# Motor.net
KiCad netlist of a schematic drawn in EAGLE
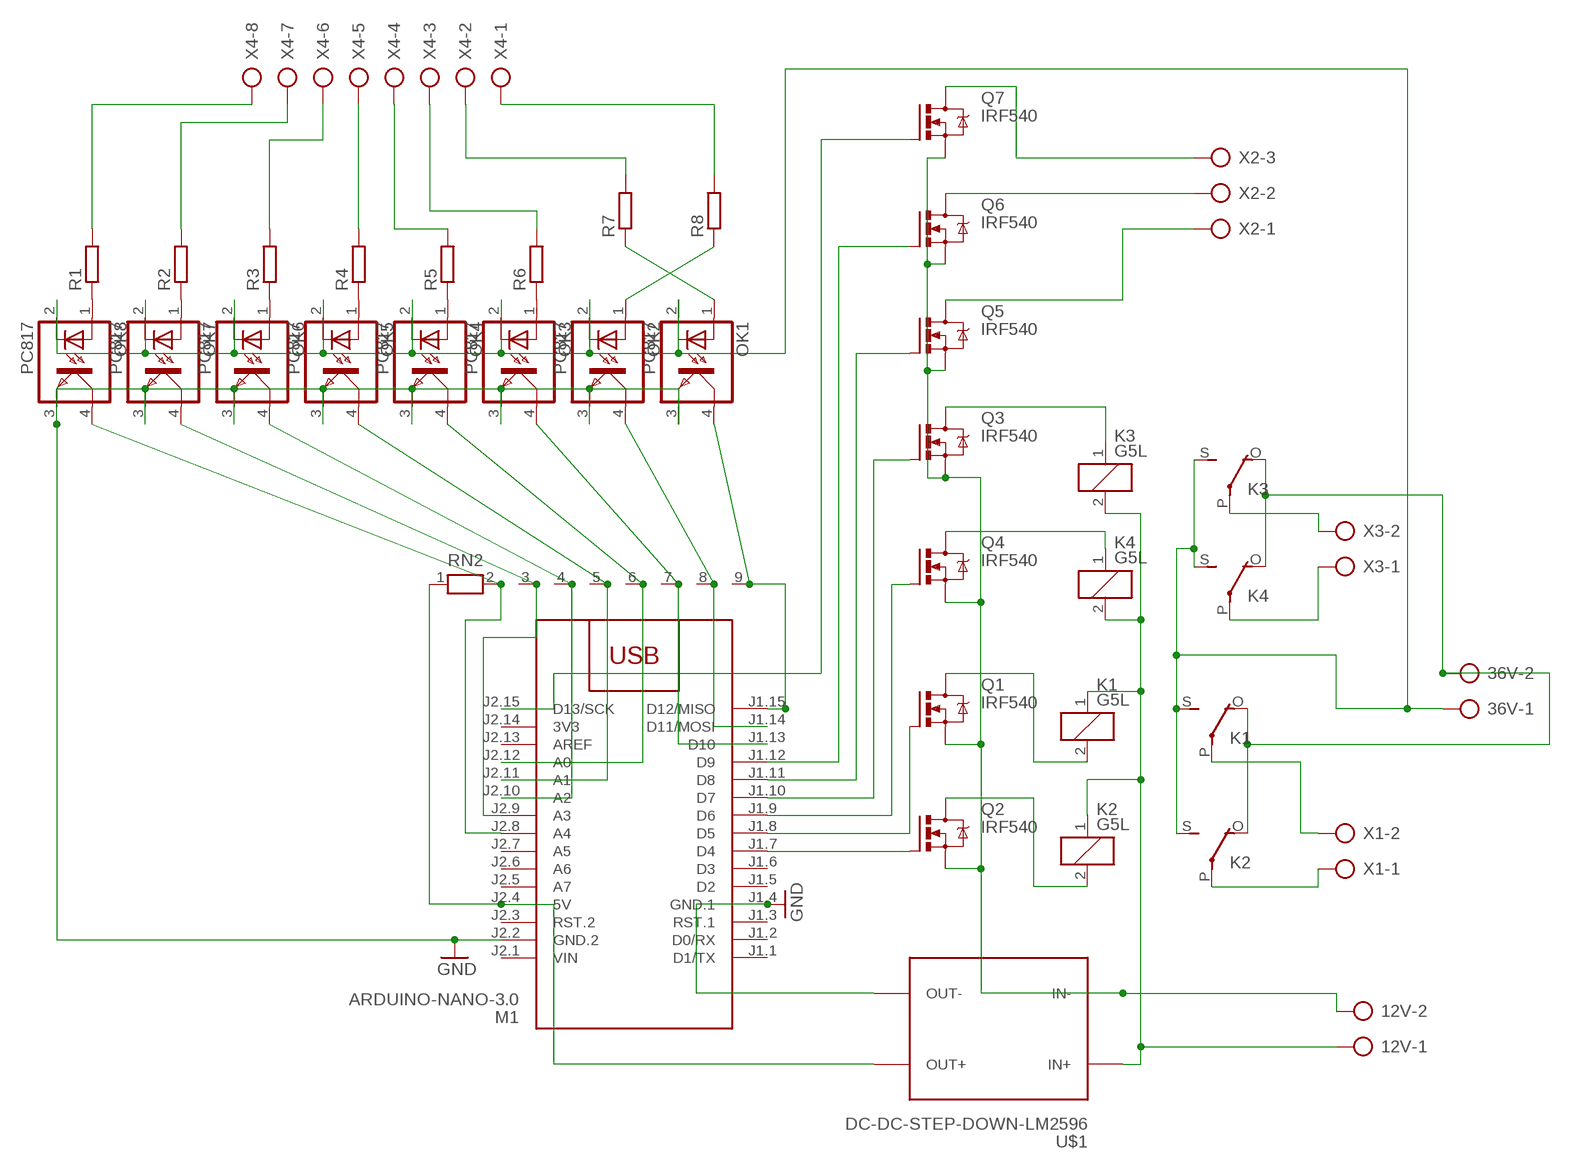
[diagram p0: schematic, sheet 1]

(export (version "E")
  (design (tool "Eeschema 10.0.6"))
  (components
    (comp (ref "12V")
      (value "AK300/2")
      (footprint "eagle-import:AK300_2")
      (libsource (lib "eagle-import") (part "AK300/2"))
    )
    (comp (ref "36V")
      (value "AK300/2")
      (footprint "eagle-import:AK300_2")
      (libsource (lib "eagle-import") (part "AK300/2"))
    )
    (comp (ref "K1")
      (value "G5L")
      (footprint "eagle-import:G5LE")
      (libsource (lib "eagle-import") (part "G5L"))
    )
    (comp (ref "K2")
      (value "G5L")
      (footprint "eagle-import:G5LE")
      (libsource (lib "eagle-import") (part "G5L"))
    )
    (comp (ref "K3")
      (value "G5L")
      (footprint "eagle-import:G5LE")
      (libsource (lib "eagle-import") (part "G5L"))
    )
    (comp (ref "K4")
      (value "G5L")
      (footprint "eagle-import:G5LE")
      (libsource (lib "eagle-import") (part "G5L"))
    )
    (comp (ref "M1")
      (value "ARDUINO-NANO-3.0")
      (footprint "eagle-import:ARDUINO-NANO-3.0")
      (libsource (lib "eagle-import") (part "ARDUINO-NANO-3.0"))
    )
    (comp (ref "OK1")
      (value "PC817")
      (footprint "eagle-import:DIL04")
      (fields (field (name "MPN") "PC817X4J000F"))
      (libsource (lib "eagle-import") (part "PC817"))
    )
    (comp (ref "OK2")
      (value "PC817")
      (footprint "eagle-import:DIL04")
      (fields (field (name "MPN") "PC817X4J000F"))
      (libsource (lib "eagle-import") (part "PC817"))
    )
    (comp (ref "OK3")
      (value "PC817")
      (footprint "eagle-import:DIL04")
      (fields (field (name "MPN") "PC817X4J000F"))
      (libsource (lib "eagle-import") (part "PC817"))
    )
    (comp (ref "OK4")
      (value "PC817")
      (footprint "eagle-import:DIL04")
      (fields (field (name "MPN") "PC817X4J000F"))
      (libsource (lib "eagle-import") (part "PC817"))
    )
    (comp (ref "OK5")
      (value "PC817")
      (footprint "eagle-import:DIL04")
      (fields (field (name "MPN") "PC817X4J000F"))
      (libsource (lib "eagle-import") (part "PC817"))
    )
    (comp (ref "OK6")
      (value "PC817")
      (footprint "eagle-import:DIL04")
      (fields (field (name "MPN") "PC817X4J000F"))
      (libsource (lib "eagle-import") (part "PC817"))
    )
    (comp (ref "OK7")
      (value "PC817")
      (footprint "eagle-import:DIL04")
      (fields (field (name "MPN") "PC817X4J000F"))
      (libsource (lib "eagle-import") (part "PC817"))
    )
    (comp (ref "OK8")
      (value "PC817")
      (footprint "eagle-import:DIL04")
      (fields (field (name "MPN") "PC817X4J000F"))
      (libsource (lib "eagle-import") (part "PC817"))
    )
    (comp (ref "Q1")
      (value "IRF540")
      (footprint "eagle-import:TO220BV")
      (libsource (lib "eagle-import") (part "IRF540"))
    )
    (comp (ref "Q2")
      (value "IRF540")
      (footprint "eagle-import:TO220BV")
      (libsource (lib "eagle-import") (part "IRF540"))
    )
    (comp (ref "Q3")
      (value "IRF540")
      (footprint "eagle-import:TO220BV")
      (libsource (lib "eagle-import") (part "IRF540"))
    )
    (comp (ref "Q4")
      (value "IRF540")
      (footprint "eagle-import:TO220BV")
      (libsource (lib "eagle-import") (part "IRF540"))
    )
    (comp (ref "Q5")
      (value "IRF540")
      (footprint "eagle-import:TO220BV")
      (libsource (lib "eagle-import") (part "IRF540"))
    )
    (comp (ref "Q6")
      (value "IRF540")
      (footprint "eagle-import:TO220BV")
      (libsource (lib "eagle-import") (part "IRF540"))
    )
    (comp (ref "Q7")
      (value "IRF540")
      (footprint "eagle-import:TO220BV")
      (libsource (lib "eagle-import") (part "IRF540"))
    )
    (comp (ref "R1")
      (value "R-EU_0204/7")
      (footprint "eagle-import:0204_7")
      (libsource (lib "eagle-import") (part "R-EU_0204/7"))
    )
    (comp (ref "R2")
      (value "R-EU_0204/7")
      (footprint "eagle-import:0204_7")
      (libsource (lib "eagle-import") (part "R-EU_0204/7"))
    )
    (comp (ref "R3")
      (value "R-EU_0204/7")
      (footprint "eagle-import:0204_7")
      (libsource (lib "eagle-import") (part "R-EU_0204/7"))
    )
    (comp (ref "R4")
      (value "R-EU_0204/7")
      (footprint "eagle-import:0204_7")
      (libsource (lib "eagle-import") (part "R-EU_0204/7"))
    )
    (comp (ref "R5")
      (value "R-EU_0204/7")
      (footprint "eagle-import:0204_7")
      (libsource (lib "eagle-import") (part "R-EU_0204/7"))
    )
    (comp (ref "R6")
      (value "R-EU_0204/7")
      (footprint "eagle-import:0204_7")
      (libsource (lib "eagle-import") (part "R-EU_0204/7"))
    )
    (comp (ref "R7")
      (value "R-EU_0204/7")
      (footprint "eagle-import:0204_7")
      (libsource (lib "eagle-import") (part "R-EU_0204/7"))
    )
    (comp (ref "R8")
      (value "R-EU_0204/7")
      (footprint "eagle-import:0204_7")
      (libsource (lib "eagle-import") (part "R-EU_0204/7"))
    )
    (comp (ref "RN2")
      (value "RN08")
      (footprint "eagle-import:RN-9")
      (libsource (lib "eagle-import") (part "RN08"))
    )
    (comp (ref "U$1")
      (value "DC-DC-STEP-DOWN-LM2596")
      (footprint "eagle-import:DC-DC-STEP-DOWN-LM2596")
      (libsource (lib "eagle-import") (part "DC-DC-STEP-DOWN-LM2596"))
    )
    (comp (ref "X1")
      (value "AK300/2")
      (footprint "eagle-import:AK300_2")
      (libsource (lib "eagle-import") (part "AK300/2"))
    )
    (comp (ref "X2")
      (value "AK300/3")
      (footprint "eagle-import:AK300_3")
      (libsource (lib "eagle-import") (part "AK300/3"))
    )
    (comp (ref "X3")
      (value "AK300/2")
      (footprint "eagle-import:AK300_2")
      (libsource (lib "eagle-import") (part "AK300/2"))
    )
    (comp (ref "X4")
      (value "AK300/8")
      (footprint "eagle-import:AK300_8")
      (libsource (lib "eagle-import") (part "AK300/8"))
    )
  )
  (nets
    (net (code "1") (name "/3V3") (class "Default")
      (node (ref "M1") (pin "J2.14") (pinfunction "3V3_J2.14") (pintype "power_in"))
    )
    (net (code "2") (name "/VIN") (class "Default")
      (node (ref "M1") (pin "J2.1") (pinfunction "VIN_J2.1") (pintype "power_in"))
    )
    (net (code "3") (name "GND") (class "Default")
      (node (ref "M1") (pin "J1.4") (pinfunction "GND.1_J1.4") (pintype "power_in"))
      (node (ref "M1") (pin "J2.2") (pinfunction "GND.2_J2.2") (pintype "power_in"))
      (node (ref "OK1") (pin "3") (pinfunction "EMIT_3") (pintype "passive"))
      (node (ref "OK2") (pin "3") (pinfunction "EMIT_3") (pintype "passive"))
      (node (ref "OK3") (pin "3") (pinfunction "EMIT_3") (pintype "passive"))
      (node (ref "OK4") (pin "3") (pinfunction "EMIT_3") (pintype "passive"))
      (node (ref "OK5") (pin "3") (pinfunction "EMIT_3") (pintype "passive"))
      (node (ref "OK6") (pin "3") (pinfunction "EMIT_3") (pintype "passive"))
      (node (ref "OK7") (pin "3") (pinfunction "EMIT_3") (pintype "passive"))
      (node (ref "OK8") (pin "3") (pinfunction "EMIT_3") (pintype "passive"))
      (node (ref "U$1") (pin "OUT-") (pinfunction "OUT-_OUT-") (pintype "bidirectional"))
    )
    (net (code "4") (name "Net-(12VA-KL)") (class "Default")
      (node (ref "12V") (pin "1") (pinfunction "KL_1") (pintype "passive"))
      (node (ref "K1") (pin "1") (pinfunction "1_1") (pintype "passive"))
      (node (ref "K2") (pin "1") (pinfunction "1_1") (pintype "passive"))
      (node (ref "K3") (pin "2") (pinfunction "2_2") (pintype "passive"))
      (node (ref "K4") (pin "2") (pinfunction "2_2") (pintype "passive"))
      (node (ref "U$1") (pin "IN+") (pinfunction "IN+_IN+") (pintype "bidirectional"))
    )
    (net (code "5") (name "Net-(12VB-KL)") (class "Default")
      (node (ref "12V") (pin "2") (pinfunction "KL_2") (pintype "passive"))
      (node (ref "Q1") (pin "S") (pinfunction "S_S") (pintype "passive"))
      (node (ref "Q2") (pin "S") (pinfunction "S_S") (pintype "passive"))
      (node (ref "Q3") (pin "S") (pinfunction "S_S") (pintype "passive"))
      (node (ref "Q4") (pin "S") (pinfunction "S_S") (pintype "passive"))
      (node (ref "Q5") (pin "S") (pinfunction "S_S") (pintype "passive"))
      (node (ref "Q6") (pin "S") (pinfunction "S_S") (pintype "passive"))
      (node (ref "Q7") (pin "S") (pinfunction "S_S") (pintype "passive"))
      (node (ref "U$1") (pin "IN-") (pinfunction "IN-_IN-") (pintype "bidirectional"))
    )
    (net (code "6") (name "Net-(36VA-KL)") (class "Default")
      (node (ref "36V") (pin "1") (pinfunction "KL_1") (pintype "passive"))
      (node (ref "K1") (pin "S") (pinfunction "S_S") (pintype "passive"))
      (node (ref "K2") (pin "S") (pinfunction "S_S") (pintype "passive"))
      (node (ref "K3") (pin "S") (pinfunction "S_S") (pintype "passive"))
      (node (ref "K4") (pin "S") (pinfunction "S_S") (pintype "passive"))
      (node (ref "OK1") (pin "2") (pinfunction "C_2") (pintype "passive"))
      (node (ref "OK2") (pin "2") (pinfunction "C_2") (pintype "passive"))
      (node (ref "OK3") (pin "2") (pinfunction "C_2") (pintype "passive"))
      (node (ref "OK4") (pin "2") (pinfunction "C_2") (pintype "passive"))
      (node (ref "OK5") (pin "2") (pinfunction "C_2") (pintype "passive"))
      (node (ref "OK6") (pin "2") (pinfunction "C_2") (pintype "passive"))
      (node (ref "OK7") (pin "2") (pinfunction "C_2") (pintype "passive"))
      (node (ref "OK8") (pin "2") (pinfunction "C_2") (pintype "passive"))
    )
    (net (code "7") (name "Net-(36VB-KL)") (class "Default")
      (node (ref "36V") (pin "2") (pinfunction "KL_2") (pintype "passive"))
      (node (ref "K1") (pin "O") (pinfunction "O_O") (pintype "passive"))
      (node (ref "K2") (pin "O") (pinfunction "O_O") (pintype "passive"))
      (node (ref "K3") (pin "O") (pinfunction "O_O") (pintype "passive"))
      (node (ref "K4") (pin "O") (pinfunction "O_O") (pintype "passive"))
    )
    (net (code "8") (name "Net-(K1-Pad2)") (class "Default")
      (node (ref "K1") (pin "2") (pinfunction "2_2") (pintype "passive"))
      (node (ref "Q1") (pin "D") (pinfunction "D_D") (pintype "passive"))
    )
    (net (code "9") (name "Net-(K2-Pad2)") (class "Default")
      (node (ref "K2") (pin "2") (pinfunction "2_2") (pintype "passive"))
      (node (ref "Q2") (pin "D") (pinfunction "D_D") (pintype "passive"))
    )
    (net (code "10") (name "Net-(K3-Pad1)") (class "Default")
      (node (ref "K3") (pin "1") (pinfunction "1_1") (pintype "passive"))
      (node (ref "Q3") (pin "D") (pinfunction "D_D") (pintype "passive"))
    )
    (net (code "11") (name "Net-(K4-Pad1)") (class "Default")
      (node (ref "K4") (pin "1") (pinfunction "1_1") (pintype "passive"))
      (node (ref "Q4") (pin "D") (pinfunction "D_D") (pintype "passive"))
    )
    (net (code "12") (name "Net-(M1-5V)") (class "Default")
      (node (ref "M1") (pin "J2.4") (pinfunction "5V_J2.4") (pintype "power_in"))
      (node (ref "RN2") (pin "1") (pinfunction "1_1") (pintype "passive"))
      (node (ref "U$1") (pin "OUT+") (pinfunction "OUT+_OUT+") (pintype "bidirectional"))
    )
    (net (code "13") (name "Net-(M1-A0)") (class "Default")
      (node (ref "M1") (pin "J2.12") (pinfunction "A0_J2.12") (pintype "bidirectional"))
      (node (ref "OK4") (pin "4") (pinfunction "COL_4") (pintype "passive"))
      (node (ref "RN2") (pin "6") (pinfunction "6_6") (pintype "passive"))
    )
    (net (code "14") (name "Net-(M1-A1)") (class "Default")
      (node (ref "M1") (pin "J2.11") (pinfunction "A1_J2.11") (pintype "bidirectional"))
      (node (ref "OK5") (pin "4") (pinfunction "COL_4") (pintype "passive"))
      (node (ref "RN2") (pin "5") (pinfunction "5_5") (pintype "passive"))
    )
    (net (code "15") (name "Net-(M1-A2)") (class "Default")
      (node (ref "M1") (pin "J2.10") (pinfunction "A2_J2.10") (pintype "bidirectional"))
      (node (ref "OK6") (pin "4") (pinfunction "COL_4") (pintype "passive"))
      (node (ref "RN2") (pin "4") (pinfunction "4_4") (pintype "passive"))
    )
    (net (code "16") (name "Net-(M1-A3)") (class "Default")
      (node (ref "M1") (pin "J2.9") (pinfunction "A3_J2.9") (pintype "bidirectional"))
      (node (ref "OK7") (pin "4") (pinfunction "COL_4") (pintype "passive"))
      (node (ref "RN2") (pin "3") (pinfunction "3_3") (pintype "passive"))
    )
    (net (code "17") (name "Net-(M1-A4)") (class "Default")
      (node (ref "M1") (pin "J2.8") (pinfunction "A4_J2.8") (pintype "bidirectional"))
      (node (ref "OK8") (pin "4") (pinfunction "COL_4") (pintype "passive"))
      (node (ref "RN2") (pin "2") (pinfunction "2_2") (pintype "passive"))
    )
    (net (code "18") (name "Net-(M1-D4)") (class "Default")
      (node (ref "M1") (pin "J1.7") (pinfunction "D4_J1.7") (pintype "bidirectional"))
      (node (ref "Q2") (pin "G") (pinfunction "G_G") (pintype "passive"))
    )
    (net (code "19") (name "Net-(M1-D5)") (class "Default")
      (node (ref "M1") (pin "J1.8") (pinfunction "D5_J1.8") (pintype "bidirectional"))
      (node (ref "Q1") (pin "G") (pinfunction "G_G") (pintype "passive"))
    )
    (net (code "20") (name "Net-(M1-D6)") (class "Default")
      (node (ref "M1") (pin "J1.9") (pinfunction "D6_J1.9") (pintype "bidirectional"))
      (node (ref "Q4") (pin "G") (pinfunction "G_G") (pintype "passive"))
    )
    (net (code "21") (name "Net-(M1-D7)") (class "Default")
      (node (ref "M1") (pin "J1.10") (pinfunction "D7_J1.10") (pintype "bidirectional"))
      (node (ref "Q3") (pin "G") (pinfunction "G_G") (pintype "passive"))
    )
    (net (code "22") (name "Net-(M1-D8)") (class "Default")
      (node (ref "M1") (pin "J1.11") (pinfunction "D8_J1.11") (pintype "bidirectional"))
      (node (ref "Q5") (pin "G") (pinfunction "G_G") (pintype "passive"))
    )
    (net (code "23") (name "Net-(M1-D9)") (class "Default")
      (node (ref "M1") (pin "J1.12") (pinfunction "D9_J1.12") (pintype "bidirectional"))
      (node (ref "Q6") (pin "G") (pinfunction "G_G") (pintype "passive"))
    )
    (net (code "24") (name "Net-(M1-D10)") (class "Default")
      (node (ref "M1") (pin "J1.13") (pinfunction "D10_J1.13") (pintype "bidirectional"))
      (node (ref "OK3") (pin "4") (pinfunction "COL_4") (pintype "passive"))
      (node (ref "RN2") (pin "7") (pinfunction "7_7") (pintype "passive"))
    )
    (net (code "25") (name "Net-(M1-D11{slash}MOSI)") (class "Default")
      (node (ref "M1") (pin "J1.14") (pinfunction "D11/MOSI_J1.14") (pintype "bidirectional"))
      (node (ref "OK2") (pin "4") (pinfunction "COL_4") (pintype "passive"))
      (node (ref "RN2") (pin "8") (pinfunction "8_8") (pintype "passive"))
    )
    (net (code "26") (name "Net-(M1-D12{slash}MISO)") (class "Default")
      (node (ref "M1") (pin "J1.15") (pinfunction "D12/MISO_J1.15") (pintype "bidirectional"))
      (node (ref "OK1") (pin "4") (pinfunction "COL_4") (pintype "passive"))
      (node (ref "RN2") (pin "9") (pinfunction "9_9") (pintype "passive"))
    )
    (net (code "27") (name "Net-(M1-D13{slash}SCK)") (class "Default")
      (node (ref "M1") (pin "J2.15") (pinfunction "D13/SCK_J2.15") (pintype "bidirectional"))
      (node (ref "Q7") (pin "G") (pinfunction "G_G") (pintype "passive"))
    )
    (net (code "28") (name "Net-(OK1-A)") (class "Default")
      (node (ref "OK1") (pin "1") (pinfunction "A_1") (pintype "passive"))
      (node (ref "R7") (pin "1") (pinfunction "1_1") (pintype "passive"))
    )
    (net (code "29") (name "Net-(OK2-A)") (class "Default")
      (node (ref "OK2") (pin "1") (pinfunction "A_1") (pintype "passive"))
      (node (ref "R8") (pin "1") (pinfunction "1_1") (pintype "passive"))
    )
    (net (code "30") (name "Net-(OK3-A)") (class "Default")
      (node (ref "OK3") (pin "1") (pinfunction "A_1") (pintype "passive"))
      (node (ref "R6") (pin "1") (pinfunction "1_1") (pintype "passive"))
    )
    (net (code "31") (name "Net-(OK4-A)") (class "Default")
      (node (ref "OK4") (pin "1") (pinfunction "A_1") (pintype "passive"))
      (node (ref "R5") (pin "1") (pinfunction "1_1") (pintype "passive"))
    )
    (net (code "32") (name "Net-(OK5-A)") (class "Default")
      (node (ref "OK5") (pin "1") (pinfunction "A_1") (pintype "passive"))
      (node (ref "R4") (pin "1") (pinfunction "1_1") (pintype "passive"))
    )
    (net (code "33") (name "Net-(OK6-A)") (class "Default")
      (node (ref "OK6") (pin "1") (pinfunction "A_1") (pintype "passive"))
      (node (ref "R3") (pin "1") (pinfunction "1_1") (pintype "passive"))
    )
    (net (code "34") (name "Net-(OK7-A)") (class "Default")
      (node (ref "OK7") (pin "1") (pinfunction "A_1") (pintype "passive"))
      (node (ref "R2") (pin "1") (pinfunction "1_1") (pintype "passive"))
    )
    (net (code "35") (name "Net-(OK8-A)") (class "Default")
      (node (ref "OK8") (pin "1") (pinfunction "A_1") (pintype "passive"))
      (node (ref "R1") (pin "1") (pinfunction "1_1") (pintype "passive"))
    )
    (net (code "36") (name "Net-(X1A-KL)") (class "Default")
      (node (ref "K2") (pin "P") (pinfunction "P_P") (pintype "passive"))
      (node (ref "X1") (pin "1") (pinfunction "KL_1") (pintype "passive"))
    )
    (net (code "37") (name "Net-(X1B-KL)") (class "Default")
      (node (ref "K1") (pin "P") (pinfunction "P_P") (pintype "passive"))
      (node (ref "X1") (pin "2") (pinfunction "KL_2") (pintype "passive"))
    )
    (net (code "38") (name "Net-(X2A-KL)") (class "Default")
      (node (ref "Q5") (pin "D") (pinfunction "D_D") (pintype "passive"))
      (node (ref "X2") (pin "1") (pinfunction "KL_1") (pintype "passive"))
    )
    (net (code "39") (name "Net-(X2B-KL)") (class "Default")
      (node (ref "Q6") (pin "D") (pinfunction "D_D") (pintype "passive"))
      (node (ref "X2") (pin "2") (pinfunction "KL_2") (pintype "passive"))
    )
    (net (code "40") (name "Net-(X2C-KL)") (class "Default")
      (node (ref "Q7") (pin "D") (pinfunction "D_D") (pintype "passive"))
      (node (ref "X2") (pin "3") (pinfunction "KL_3") (pintype "passive"))
    )
    (net (code "41") (name "Net-(X3A-KL)") (class "Default")
      (node (ref "K4") (pin "P") (pinfunction "P_P") (pintype "passive"))
      (node (ref "X3") (pin "1") (pinfunction "KL_1") (pintype "passive"))
    )
    (net (code "42") (name "Net-(X3B-KL)") (class "Default")
      (node (ref "K3") (pin "P") (pinfunction "P_P") (pintype "passive"))
      (node (ref "X3") (pin "2") (pinfunction "KL_2") (pintype "passive"))
    )
    (net (code "43") (name "Net-(X4A-KL)") (class "Default")
      (node (ref "R8") (pin "2") (pinfunction "2_2") (pintype "passive"))
      (node (ref "X4") (pin "1") (pinfunction "KL_1") (pintype "passive"))
    )
    (net (code "44") (name "Net-(X4B-KL)") (class "Default")
      (node (ref "R7") (pin "2") (pinfunction "2_2") (pintype "passive"))
      (node (ref "X4") (pin "2") (pinfunction "KL_2") (pintype "passive"))
    )
    (net (code "45") (name "Net-(X4C-KL)") (class "Default")
      (node (ref "R6") (pin "2") (pinfunction "2_2") (pintype "passive"))
      (node (ref "X4") (pin "3") (pinfunction "KL_3") (pintype "passive"))
    )
    (net (code "46") (name "Net-(X4D-KL)") (class "Default")
      (node (ref "R5") (pin "2") (pinfunction "2_2") (pintype "passive"))
      (node (ref "X4") (pin "4") (pinfunction "KL_4") (pintype "passive"))
    )
    (net (code "47") (name "Net-(X4E-KL)") (class "Default")
      (node (ref "R4") (pin "2") (pinfunction "2_2") (pintype "passive"))
      (node (ref "X4") (pin "5") (pinfunction "KL_5") (pintype "passive"))
    )
    (net (code "48") (name "Net-(X4F-KL)") (class "Default")
      (node (ref "R3") (pin "2") (pinfunction "2_2") (pintype "passive"))
      (node (ref "X4") (pin "6") (pinfunction "KL_6") (pintype "passive"))
    )
    (net (code "49") (name "Net-(X4G-KL)") (class "Default")
      (node (ref "R2") (pin "2") (pinfunction "2_2") (pintype "passive"))
      (node (ref "X4") (pin "7") (pinfunction "KL_7") (pintype "passive"))
    )
    (net (code "50") (name "Net-(X4H-KL)") (class "Default")
      (node (ref "R1") (pin "2") (pinfunction "2_2") (pintype "passive"))
      (node (ref "X4") (pin "8") (pinfunction "KL_8") (pintype "passive"))
    )
    (net (code "51") (name "unconnected-(M1-A5-PadJ2.7)") (class "Default")
      (node (ref "M1") (pin "J2.7") (pinfunction "A5_J2.7") (pintype "bidirectional"))
    )
    (net (code "52") (name "unconnected-(M1-A6-PadJ2.6)") (class "Default")
      (node (ref "M1") (pin "J2.6") (pinfunction "A6_J2.6") (pintype "bidirectional"))
    )
    (net (code "53") (name "unconnected-(M1-A7-PadJ2.5)") (class "Default")
      (node (ref "M1") (pin "J2.5") (pinfunction "A7_J2.5") (pintype "bidirectional"))
    )
    (net (code "54") (name "unconnected-(M1-AREF-PadJ2.13)") (class "Default")
      (node (ref "M1") (pin "J2.13") (pinfunction "AREF_J2.13") (pintype "bidirectional"))
    )
    (net (code "55") (name "unconnected-(M1-D0{slash}RX-PadJ1.2)") (class "Default")
      (node (ref "M1") (pin "J1.2") (pinfunction "D0/RX_J1.2") (pintype "bidirectional"))
    )
    (net (code "56") (name "unconnected-(M1-D1{slash}TX-PadJ1.1)") (class "Default")
      (node (ref "M1") (pin "J1.1") (pinfunction "D1/TX_J1.1") (pintype "bidirectional"))
    )
    (net (code "57") (name "unconnected-(M1-D2-PadJ1.5)") (class "Default")
      (node (ref "M1") (pin "J1.5") (pinfunction "D2_J1.5") (pintype "bidirectional"))
    )
    (net (code "58") (name "unconnected-(M1-D3-PadJ1.6)") (class "Default")
      (node (ref "M1") (pin "J1.6") (pinfunction "D3_J1.6") (pintype "bidirectional"))
    )
    (net (code "59") (name "unconnected-(M1-RST.1-PadJ1.3)") (class "Default")
      (node (ref "M1") (pin "J1.3") (pinfunction "RST.1_J1.3") (pintype "bidirectional"))
    )
    (net (code "60") (name "unconnected-(M1-RST.2-PadJ2.3)") (class "Default")
      (node (ref "M1") (pin "J2.3") (pinfunction "RST.2_J2.3") (pintype "bidirectional"))
    )
  )
)
